# control-surface-left.net
KiCad netlist of a schematic drawn in EAGLE
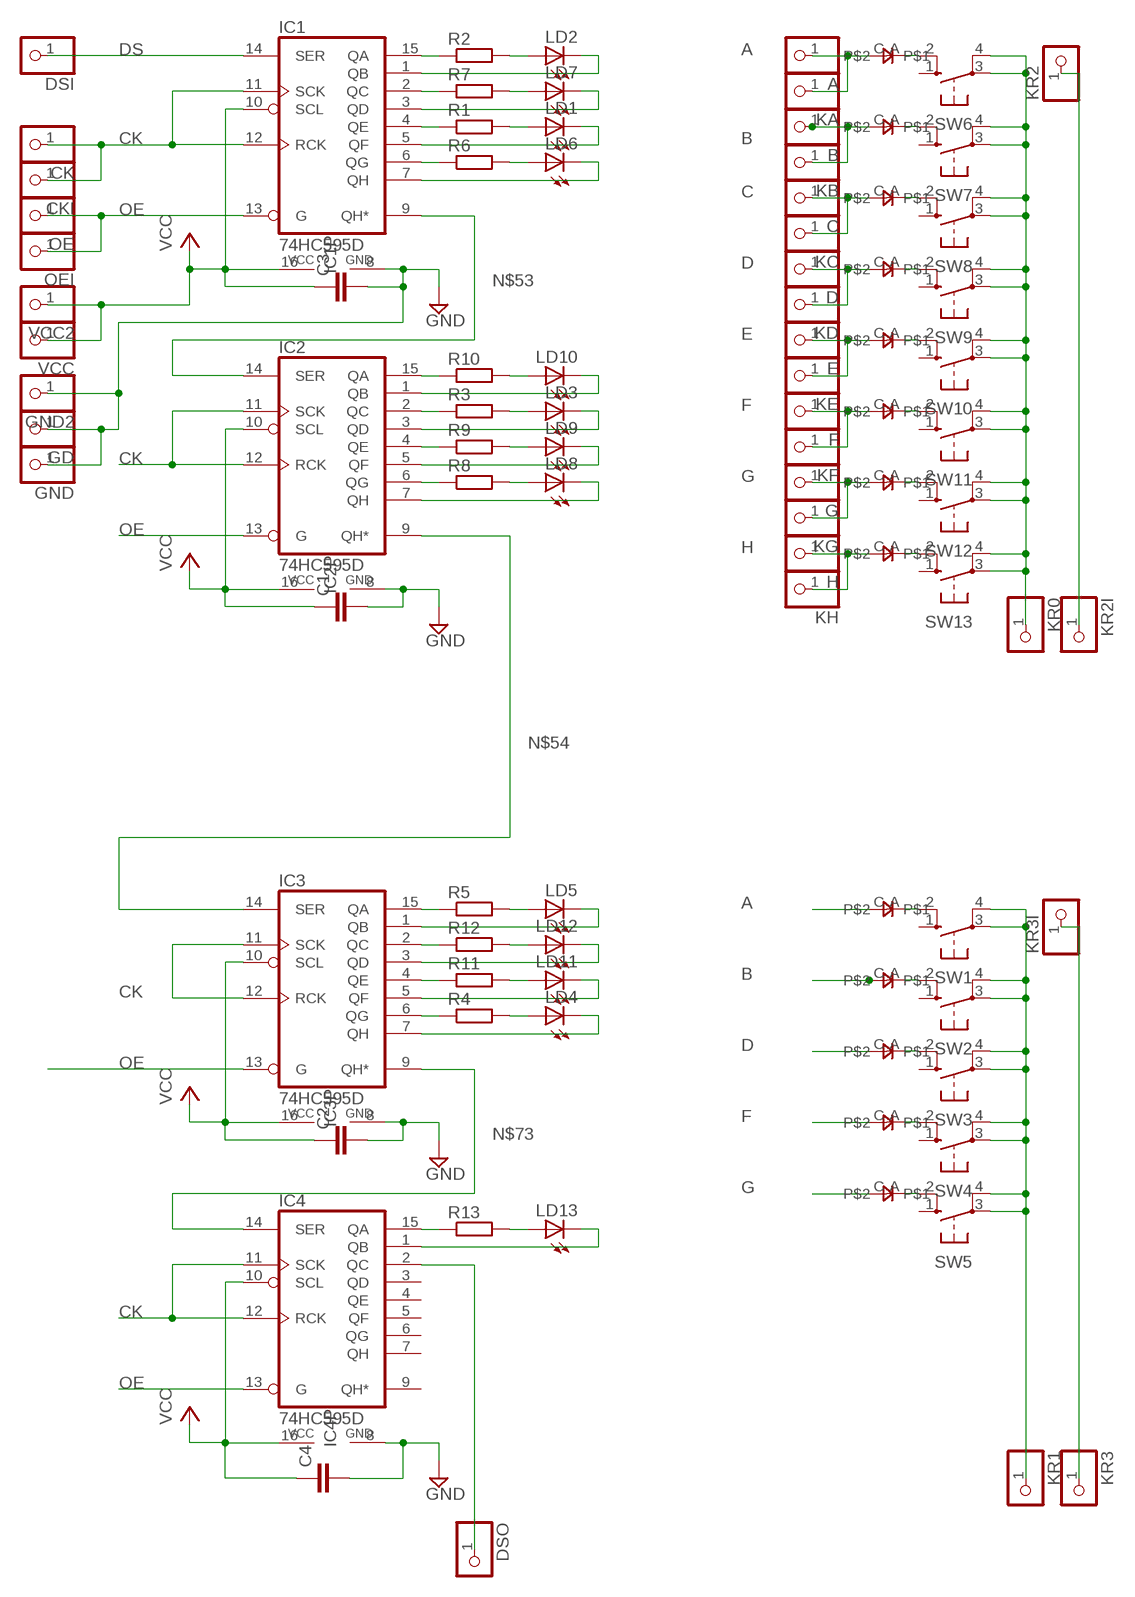
[diagram p0: schematic, sheet 1]

(export (version "E")
  (design (tool "Eeschema 10.0.6"))
  (components
    (comp (ref "A")
      (value "PINHD-1X1")
      (footprint "eagle-import:1X01")
      (libsource (lib "eagle-import") (part "PINHD-1X1"))
    )
    (comp (ref "B")
      (value "PINHD-1X1")
      (footprint "eagle-import:1X01")
      (libsource (lib "eagle-import") (part "PINHD-1X1"))
    )
    (comp (ref "C")
      (value "PINHD-1X1")
      (footprint "eagle-import:1X01")
      (libsource (lib "eagle-import") (part "PINHD-1X1"))
    )
    (comp (ref "C1")
      (value "C-EUC0805")
      (footprint "eagle-import:C0805")
      (libsource (lib "eagle-import") (part "C-EUC0805"))
    )
    (comp (ref "C2")
      (value "C-EUC0805")
      (footprint "eagle-import:C0805")
      (libsource (lib "eagle-import") (part "C-EUC0805"))
    )
    (comp (ref "C3")
      (value "C-EUC0805")
      (footprint "eagle-import:C0805")
      (libsource (lib "eagle-import") (part "C-EUC0805"))
    )
    (comp (ref "C4")
      (value "C-EUC0805")
      (footprint "eagle-import:C0805")
      (libsource (lib "eagle-import") (part "C-EUC0805"))
    )
    (comp (ref "CK")
      (value "PINHD-1X1")
      (footprint "eagle-import:1X01")
      (libsource (lib "eagle-import") (part "PINHD-1X1"))
    )
    (comp (ref "CKI")
      (value "PINHD-1X1")
      (footprint "eagle-import:1X01")
      (libsource (lib "eagle-import") (part "PINHD-1X1"))
    )
    (comp (ref "D")
      (value "PINHD-1X1")
      (footprint "eagle-import:1X01")
      (libsource (lib "eagle-import") (part "PINHD-1X1"))
    )
    (comp (ref "D1")
      (value "0805DIODE")
      (footprint "eagle-import:0805DIODE")
      (libsource (lib "eagle-import") (part "0805DIODE"))
    )
    (comp (ref "D2")
      (value "0805DIODE")
      (footprint "eagle-import:0805DIODE")
      (libsource (lib "eagle-import") (part "0805DIODE"))
    )
    (comp (ref "D3")
      (value "0805DIODE")
      (footprint "eagle-import:0805DIODE")
      (libsource (lib "eagle-import") (part "0805DIODE"))
    )
    (comp (ref "D4")
      (value "0805DIODE")
      (footprint "eagle-import:0805DIODE")
      (libsource (lib "eagle-import") (part "0805DIODE"))
    )
    (comp (ref "D5")
      (value "0805DIODE")
      (footprint "eagle-import:0805DIODE")
      (libsource (lib "eagle-import") (part "0805DIODE"))
    )
    (comp (ref "D6")
      (value "0805DIODE")
      (footprint "eagle-import:0805DIODE")
      (libsource (lib "eagle-import") (part "0805DIODE"))
    )
    (comp (ref "D7")
      (value "0805DIODE")
      (footprint "eagle-import:0805DIODE")
      (libsource (lib "eagle-import") (part "0805DIODE"))
    )
    (comp (ref "D8")
      (value "0805DIODE")
      (footprint "eagle-import:0805DIODE")
      (libsource (lib "eagle-import") (part "0805DIODE"))
    )
    (comp (ref "D9")
      (value "0805DIODE")
      (footprint "eagle-import:0805DIODE")
      (libsource (lib "eagle-import") (part "0805DIODE"))
    )
    (comp (ref "D10")
      (value "0805DIODE")
      (footprint "eagle-import:0805DIODE")
      (libsource (lib "eagle-import") (part "0805DIODE"))
    )
    (comp (ref "D11")
      (value "0805DIODE")
      (footprint "eagle-import:0805DIODE")
      (libsource (lib "eagle-import") (part "0805DIODE"))
    )
    (comp (ref "D12")
      (value "0805DIODE")
      (footprint "eagle-import:0805DIODE")
      (libsource (lib "eagle-import") (part "0805DIODE"))
    )
    (comp (ref "D13")
      (value "0805DIODE")
      (footprint "eagle-import:0805DIODE")
      (libsource (lib "eagle-import") (part "0805DIODE"))
    )
    (comp (ref "DSI")
      (value "PINHD-1X1")
      (footprint "eagle-import:1X01")
      (libsource (lib "eagle-import") (part "PINHD-1X1"))
    )
    (comp (ref "DSO")
      (value "PINHD-1X1")
      (footprint "eagle-import:1X01")
      (libsource (lib "eagle-import") (part "PINHD-1X1"))
    )
    (comp (ref "E")
      (value "PINHD-1X1")
      (footprint "eagle-import:1X01")
      (libsource (lib "eagle-import") (part "PINHD-1X1"))
    )
    (comp (ref "F")
      (value "PINHD-1X1")
      (footprint "eagle-import:1X01")
      (libsource (lib "eagle-import") (part "PINHD-1X1"))
    )
    (comp (ref "G")
      (value "PINHD-1X1")
      (footprint "eagle-import:1X01")
      (libsource (lib "eagle-import") (part "PINHD-1X1"))
    )
    (comp (ref "GD")
      (value "PINHD-1X1")
      (footprint "eagle-import:1X01")
      (libsource (lib "eagle-import") (part "PINHD-1X1"))
    )
    (comp (ref "GND")
      (value "PINHD-1X1")
      (footprint "eagle-import:1X01")
      (libsource (lib "eagle-import") (part "PINHD-1X1"))
    )
    (comp (ref "GND2")
      (value "PINHD-1X1")
      (footprint "eagle-import:1X01")
      (libsource (lib "eagle-import") (part "PINHD-1X1"))
    )
    (comp (ref "H")
      (value "PINHD-1X1")
      (footprint "eagle-import:1X01")
      (libsource (lib "eagle-import") (part "PINHD-1X1"))
    )
    (comp (ref "IC1")
      (value "74HC595D")
      (footprint "eagle-import:SO16")
      (libsource (lib "eagle-import") (part "74595DHC"))
    )
    (comp (ref "IC2")
      (value "74HC595D")
      (footprint "eagle-import:SO16")
      (libsource (lib "eagle-import") (part "74595DHC"))
    )
    (comp (ref "IC3")
      (value "74HC595D")
      (footprint "eagle-import:SO16")
      (libsource (lib "eagle-import") (part "74595DHC"))
    )
    (comp (ref "IC4")
      (value "74HC595D")
      (footprint "eagle-import:SO16")
      (libsource (lib "eagle-import") (part "74595DHC"))
    )
    (comp (ref "KA")
      (value "PINHD-1X1")
      (footprint "eagle-import:1X01")
      (libsource (lib "eagle-import") (part "PINHD-1X1"))
    )
    (comp (ref "KB")
      (value "PINHD-1X1")
      (footprint "eagle-import:1X01")
      (libsource (lib "eagle-import") (part "PINHD-1X1"))
    )
    (comp (ref "KC")
      (value "PINHD-1X1")
      (footprint "eagle-import:1X01")
      (libsource (lib "eagle-import") (part "PINHD-1X1"))
    )
    (comp (ref "KD")
      (value "PINHD-1X1")
      (footprint "eagle-import:1X01")
      (libsource (lib "eagle-import") (part "PINHD-1X1"))
    )
    (comp (ref "KE")
      (value "PINHD-1X1")
      (footprint "eagle-import:1X01")
      (libsource (lib "eagle-import") (part "PINHD-1X1"))
    )
    (comp (ref "KF")
      (value "PINHD-1X1")
      (footprint "eagle-import:1X01")
      (libsource (lib "eagle-import") (part "PINHD-1X1"))
    )
    (comp (ref "KG")
      (value "PINHD-1X1")
      (footprint "eagle-import:1X01")
      (libsource (lib "eagle-import") (part "PINHD-1X1"))
    )
    (comp (ref "KH")
      (value "PINHD-1X1")
      (footprint "eagle-import:1X01")
      (libsource (lib "eagle-import") (part "PINHD-1X1"))
    )
    (comp (ref "KR0")
      (value "PINHD-1X1")
      (footprint "eagle-import:1X01")
      (libsource (lib "eagle-import") (part "PINHD-1X1"))
    )
    (comp (ref "KR1")
      (value "PINHD-1X1")
      (footprint "eagle-import:1X01")
      (libsource (lib "eagle-import") (part "PINHD-1X1"))
    )
    (comp (ref "KR2")
      (value "PINHD-1X1")
      (footprint "eagle-import:1X01")
      (libsource (lib "eagle-import") (part "PINHD-1X1"))
    )
    (comp (ref "KR2I")
      (value "PINHD-1X1")
      (footprint "eagle-import:1X01")
      (libsource (lib "eagle-import") (part "PINHD-1X1"))
    )
    (comp (ref "KR3")
      (value "PINHD-1X1")
      (footprint "eagle-import:1X01")
      (libsource (lib "eagle-import") (part "PINHD-1X1"))
    )
    (comp (ref "KR3I")
      (value "PINHD-1X1")
      (footprint "eagle-import:1X01")
      (libsource (lib "eagle-import") (part "PINHD-1X1"))
    )
    (comp (ref "LD1")
      (value "LED3MM")
      (footprint "eagle-import:LED3MM")
      (libsource (lib "eagle-import") (part "LED3MM"))
    )
    (comp (ref "LD2")
      (value "LED3MM")
      (footprint "eagle-import:LED3MM")
      (libsource (lib "eagle-import") (part "LED3MM"))
    )
    (comp (ref "LD3")
      (value "LED3MM")
      (footprint "eagle-import:LED3MM")
      (libsource (lib "eagle-import") (part "LED3MM"))
    )
    (comp (ref "LD4")
      (value "LED3MM")
      (footprint "eagle-import:LED3MM")
      (libsource (lib "eagle-import") (part "LED3MM"))
    )
    (comp (ref "LD5")
      (value "LED3MM")
      (footprint "eagle-import:LED3MM")
      (libsource (lib "eagle-import") (part "LED3MM"))
    )
    (comp (ref "LD6")
      (value "LED3MM")
      (footprint "eagle-import:LED3MM")
      (libsource (lib "eagle-import") (part "LED3MM"))
    )
    (comp (ref "LD7")
      (value "LED3MM")
      (footprint "eagle-import:LED3MM")
      (libsource (lib "eagle-import") (part "LED3MM"))
    )
    (comp (ref "LD8")
      (value "LED3MM")
      (footprint "eagle-import:LED3MM")
      (libsource (lib "eagle-import") (part "LED3MM"))
    )
    (comp (ref "LD9")
      (value "LED3MM")
      (footprint "eagle-import:LED3MM")
      (libsource (lib "eagle-import") (part "LED3MM"))
    )
    (comp (ref "LD10")
      (value "LED3MM")
      (footprint "eagle-import:LED3MM")
      (libsource (lib "eagle-import") (part "LED3MM"))
    )
    (comp (ref "LD11")
      (value "LED3MM")
      (footprint "eagle-import:LED3MM")
      (libsource (lib "eagle-import") (part "LED3MM"))
    )
    (comp (ref "LD12")
      (value "LED3MM")
      (footprint "eagle-import:LED3MM")
      (libsource (lib "eagle-import") (part "LED3MM"))
    )
    (comp (ref "LD13")
      (value "LED3MM")
      (footprint "eagle-import:LED3MM")
      (libsource (lib "eagle-import") (part "LED3MM"))
    )
    (comp (ref "OE")
      (value "PINHD-1X1")
      (footprint "eagle-import:1X01")
      (libsource (lib "eagle-import") (part "PINHD-1X1"))
    )
    (comp (ref "OEI")
      (value "PINHD-1X1")
      (footprint "eagle-import:1X01")
      (libsource (lib "eagle-import") (part "PINHD-1X1"))
    )
    (comp (ref "R1")
      (value "R-EU_R0805")
      (footprint "eagle-import:R0805")
      (libsource (lib "eagle-import") (part "R-EU_R0805"))
    )
    (comp (ref "R2")
      (value "R-EU_R0805")
      (footprint "eagle-import:R0805")
      (libsource (lib "eagle-import") (part "R-EU_R0805"))
    )
    (comp (ref "R3")
      (value "R-EU_R0805")
      (footprint "eagle-import:R0805")
      (libsource (lib "eagle-import") (part "R-EU_R0805"))
    )
    (comp (ref "R4")
      (value "R-EU_R0805")
      (footprint "eagle-import:R0805")
      (libsource (lib "eagle-import") (part "R-EU_R0805"))
    )
    (comp (ref "R5")
      (value "R-EU_R0805")
      (footprint "eagle-import:R0805")
      (libsource (lib "eagle-import") (part "R-EU_R0805"))
    )
    (comp (ref "R6")
      (value "R-EU_R0805")
      (footprint "eagle-import:R0805")
      (libsource (lib "eagle-import") (part "R-EU_R0805"))
    )
    (comp (ref "R7")
      (value "R-EU_R0805")
      (footprint "eagle-import:R0805")
      (libsource (lib "eagle-import") (part "R-EU_R0805"))
    )
    (comp (ref "R8")
      (value "R-EU_R0805")
      (footprint "eagle-import:R0805")
      (libsource (lib "eagle-import") (part "R-EU_R0805"))
    )
    (comp (ref "R9")
      (value "R-EU_R0805")
      (footprint "eagle-import:R0805")
      (libsource (lib "eagle-import") (part "R-EU_R0805"))
    )
    (comp (ref "R10")
      (value "R-EU_R0805")
      (footprint "eagle-import:R0805")
      (libsource (lib "eagle-import") (part "R-EU_R0805"))
    )
    (comp (ref "R11")
      (value "R-EU_R0805")
      (footprint "eagle-import:R0805")
      (libsource (lib "eagle-import") (part "R-EU_R0805"))
    )
    (comp (ref "R12")
      (value "R-EU_R0805")
      (footprint "eagle-import:R0805")
      (libsource (lib "eagle-import") (part "R-EU_R0805"))
    )
    (comp (ref "R13")
      (value "R-EU_R0805")
      (footprint "eagle-import:R0805")
      (libsource (lib "eagle-import") (part "R-EU_R0805"))
    )
    (comp (ref "SW1")
      (value "40-XX")
      (footprint "eagle-import:B3F-40XX")
      (fields (field (name "MF") "OMRON COMPONENTS USA") (field (name "MPN") "B3F-4000"))
      (libsource (lib "eagle-import") (part "40-XX"))
    )
    (comp (ref "SW2")
      (value "40-XX")
      (footprint "eagle-import:B3F-40XX")
      (fields (field (name "MF") "OMRON COMPONENTS USA") (field (name "MPN") "B3F-4000"))
      (libsource (lib "eagle-import") (part "40-XX"))
    )
    (comp (ref "SW3")
      (value "40-XX")
      (footprint "eagle-import:B3F-40XX")
      (fields (field (name "MF") "OMRON COMPONENTS USA") (field (name "MPN") "B3F-4000"))
      (libsource (lib "eagle-import") (part "40-XX"))
    )
    (comp (ref "SW4")
      (value "40-XX")
      (footprint "eagle-import:B3F-40XX")
      (fields (field (name "MF") "OMRON COMPONENTS USA") (field (name "MPN") "B3F-4000"))
      (libsource (lib "eagle-import") (part "40-XX"))
    )
    (comp (ref "SW5")
      (value "40-XX")
      (footprint "eagle-import:B3F-40XX")
      (fields (field (name "MF") "OMRON COMPONENTS USA") (field (name "MPN") "B3F-4000"))
      (libsource (lib "eagle-import") (part "40-XX"))
    )
    (comp (ref "SW6")
      (value "40-XX")
      (footprint "eagle-import:B3F-40XX")
      (fields (field (name "MF") "OMRON COMPONENTS USA") (field (name "MPN") "B3F-4000"))
      (libsource (lib "eagle-import") (part "40-XX"))
    )
    (comp (ref "SW7")
      (value "40-XX")
      (footprint "eagle-import:B3F-40XX")
      (fields (field (name "MF") "OMRON COMPONENTS USA") (field (name "MPN") "B3F-4000"))
      (libsource (lib "eagle-import") (part "40-XX"))
    )
    (comp (ref "SW8")
      (value "40-XX")
      (footprint "eagle-import:B3F-40XX")
      (fields (field (name "MF") "OMRON COMPONENTS USA") (field (name "MPN") "B3F-4000"))
      (libsource (lib "eagle-import") (part "40-XX"))
    )
    (comp (ref "SW9")
      (value "40-XX")
      (footprint "eagle-import:B3F-40XX")
      (fields (field (name "MF") "OMRON COMPONENTS USA") (field (name "MPN") "B3F-4000"))
      (libsource (lib "eagle-import") (part "40-XX"))
    )
    (comp (ref "SW10")
      (value "40-XX")
      (footprint "eagle-import:B3F-40XX")
      (fields (field (name "MF") "OMRON COMPONENTS USA") (field (name "MPN") "B3F-4000"))
      (libsource (lib "eagle-import") (part "40-XX"))
    )
    (comp (ref "SW11")
      (value "40-XX")
      (footprint "eagle-import:B3F-40XX")
      (fields (field (name "MF") "OMRON COMPONENTS USA") (field (name "MPN") "B3F-4000"))
      (libsource (lib "eagle-import") (part "40-XX"))
    )
    (comp (ref "SW12")
      (value "40-XX")
      (footprint "eagle-import:B3F-40XX")
      (fields (field (name "MF") "OMRON COMPONENTS USA") (field (name "MPN") "B3F-4000"))
      (libsource (lib "eagle-import") (part "40-XX"))
    )
    (comp (ref "SW13")
      (value "40-XX")
      (footprint "eagle-import:B3F-40XX")
      (fields (field (name "MF") "OMRON COMPONENTS USA") (field (name "MPN") "B3F-4000"))
      (libsource (lib "eagle-import") (part "40-XX"))
    )
    (comp (ref "VCC")
      (value "PINHD-1X1")
      (footprint "eagle-import:1X01")
      (libsource (lib "eagle-import") (part "PINHD-1X1"))
    )
    (comp (ref "VCC2")
      (value "PINHD-1X1")
      (footprint "eagle-import:1X01")
      (libsource (lib "eagle-import") (part "PINHD-1X1"))
    )
  )
  (nets
    (net (code "1") (name "/A") (class "Default")
      (node (ref "A") (pin "1") (pinfunction "1_1") (pintype "passive"))
      (node (ref "D1") (pin "C") (pinfunction "P$1_C") (pintype "bidirectional"))
      (node (ref "D6") (pin "C") (pinfunction "P$1_C") (pintype "bidirectional"))
      (node (ref "KA") (pin "1") (pinfunction "1_1") (pintype "passive"))
    )
    (net (code "2") (name "/B") (class "Default")
      (node (ref "B") (pin "1") (pinfunction "1_1") (pintype "passive"))
      (node (ref "D2") (pin "C") (pinfunction "P$1_C") (pintype "bidirectional"))
      (node (ref "D7") (pin "C") (pinfunction "P$1_C") (pintype "bidirectional"))
      (node (ref "KB") (pin "1") (pinfunction "1_1") (pintype "passive"))
    )
    (net (code "3") (name "/C") (class "Default")
      (node (ref "C") (pin "1") (pinfunction "1_1") (pintype "passive"))
      (node (ref "D8") (pin "C") (pinfunction "P$1_C") (pintype "bidirectional"))
      (node (ref "KC") (pin "1") (pinfunction "1_1") (pintype "passive"))
    )
    (net (code "4") (name "/CK") (class "Default")
      (node (ref "CK") (pin "1") (pinfunction "1_1") (pintype "passive"))
      (node (ref "CKI") (pin "1") (pinfunction "1_1") (pintype "passive"))
      (node (ref "IC1") (pin "11") (pinfunction "SCK_11") (pintype "input"))
      (node (ref "IC1") (pin "12") (pinfunction "RCK_12") (pintype "input"))
      (node (ref "IC2") (pin "11") (pinfunction "SCK_11") (pintype "input"))
      (node (ref "IC2") (pin "12") (pinfunction "RCK_12") (pintype "input"))
      (node (ref "IC3") (pin "11") (pinfunction "SCK_11") (pintype "input"))
      (node (ref "IC3") (pin "12") (pinfunction "RCK_12") (pintype "input"))
      (node (ref "IC4") (pin "11") (pinfunction "SCK_11") (pintype "input"))
      (node (ref "IC4") (pin "12") (pinfunction "RCK_12") (pintype "input"))
    )
    (net (code "5") (name "/D") (class "Default")
      (node (ref "D") (pin "1") (pinfunction "1_1") (pintype "passive"))
      (node (ref "D3") (pin "C") (pinfunction "P$1_C") (pintype "bidirectional"))
      (node (ref "D9") (pin "C") (pinfunction "P$1_C") (pintype "bidirectional"))
      (node (ref "KD") (pin "1") (pinfunction "1_1") (pintype "passive"))
    )
    (net (code "6") (name "/DS") (class "Default")
      (node (ref "DSI") (pin "1") (pinfunction "1_1") (pintype "passive"))
      (node (ref "IC1") (pin "14") (pinfunction "SER_14") (pintype "input"))
    )
    (net (code "7") (name "/E") (class "Default")
      (node (ref "D10") (pin "C") (pinfunction "P$1_C") (pintype "bidirectional"))
      (node (ref "E") (pin "1") (pinfunction "1_1") (pintype "passive"))
      (node (ref "KE") (pin "1") (pinfunction "1_1") (pintype "passive"))
    )
    (net (code "8") (name "/F") (class "Default")
      (node (ref "D11") (pin "C") (pinfunction "P$1_C") (pintype "bidirectional"))
      (node (ref "D4") (pin "C") (pinfunction "P$1_C") (pintype "bidirectional"))
      (node (ref "F") (pin "1") (pinfunction "1_1") (pintype "passive"))
      (node (ref "KF") (pin "1") (pinfunction "1_1") (pintype "passive"))
    )
    (net (code "9") (name "/G") (class "Default")
      (node (ref "D12") (pin "C") (pinfunction "P$1_C") (pintype "bidirectional"))
      (node (ref "D5") (pin "C") (pinfunction "P$1_C") (pintype "bidirectional"))
      (node (ref "G") (pin "1") (pinfunction "1_1") (pintype "passive"))
      (node (ref "KG") (pin "1") (pinfunction "1_1") (pintype "passive"))
    )
    (net (code "10") (name "/H") (class "Default")
      (node (ref "D13") (pin "C") (pinfunction "P$1_C") (pintype "bidirectional"))
      (node (ref "H") (pin "1") (pinfunction "1_1") (pintype "passive"))
      (node (ref "KH") (pin "1") (pinfunction "1_1") (pintype "passive"))
    )
    (net (code "11") (name "/N$53") (class "Default")
      (node (ref "IC1") (pin "9") (pinfunction "QH*_9") (pintype "tri_state"))
      (node (ref "IC2") (pin "14") (pinfunction "SER_14") (pintype "input"))
    )
    (net (code "12") (name "/N$54") (class "Default")
      (node (ref "IC2") (pin "9") (pinfunction "QH*_9") (pintype "tri_state"))
      (node (ref "IC3") (pin "14") (pinfunction "SER_14") (pintype "input"))
    )
    (net (code "13") (name "/N$73") (class "Default")
      (node (ref "IC3") (pin "9") (pinfunction "QH*_9") (pintype "tri_state"))
      (node (ref "IC4") (pin "14") (pinfunction "SER_14") (pintype "input"))
    )
    (net (code "14") (name "/OE") (class "Default")
      (node (ref "IC1") (pin "13") (pinfunction "G_13") (pintype "input"))
      (node (ref "IC2") (pin "13") (pinfunction "G_13") (pintype "input"))
      (node (ref "IC3") (pin "13") (pinfunction "G_13") (pintype "input"))
      (node (ref "IC4") (pin "13") (pinfunction "G_13") (pintype "input"))
      (node (ref "OE") (pin "1") (pinfunction "1_1") (pintype "passive"))
      (node (ref "OEI") (pin "1") (pinfunction "1_1") (pintype "passive"))
    )
    (net (code "15") (name "GND") (class "Default")
      (node (ref "C1") (pin "2") (pinfunction "2_2") (pintype "passive"))
      (node (ref "C2") (pin "2") (pinfunction "2_2") (pintype "passive"))
      (node (ref "C3") (pin "2") (pinfunction "2_2") (pintype "passive"))
      (node (ref "C4") (pin "2") (pinfunction "2_2") (pintype "passive"))
      (node (ref "GD") (pin "1") (pinfunction "1_1") (pintype "passive"))
      (node (ref "GND") (pin "1") (pinfunction "1_1") (pintype "passive"))
      (node (ref "GND2") (pin "1") (pinfunction "1_1") (pintype "passive"))
      (node (ref "IC1") (pin "8") (pinfunction "GND_8") (pintype "power_in"))
      (node (ref "IC2") (pin "8") (pinfunction "GND_8") (pintype "power_in"))
      (node (ref "IC3") (pin "8") (pinfunction "GND_8") (pintype "power_in"))
      (node (ref "IC4") (pin "8") (pinfunction "GND_8") (pintype "power_in"))
    )
    (net (code "16") (name "Net-(D1-P$2)") (class "Default")
      (node (ref "D1") (pin "A") (pinfunction "P$2_A") (pintype "bidirectional"))
      (node (ref "SW1") (pin "2") (pinfunction "S1_2") (pintype "passive"))
    )
    (net (code "17") (name "Net-(D2-P$2)") (class "Default")
      (node (ref "D2") (pin "A") (pinfunction "P$2_A") (pintype "bidirectional"))
      (node (ref "SW2") (pin "2") (pinfunction "S1_2") (pintype "passive"))
    )
    (net (code "18") (name "Net-(D3-P$2)") (class "Default")
      (node (ref "D3") (pin "A") (pinfunction "P$2_A") (pintype "bidirectional"))
      (node (ref "SW3") (pin "2") (pinfunction "S1_2") (pintype "passive"))
    )
    (net (code "19") (name "Net-(D4-P$2)") (class "Default")
      (node (ref "D4") (pin "A") (pinfunction "P$2_A") (pintype "bidirectional"))
      (node (ref "SW4") (pin "2") (pinfunction "S1_2") (pintype "passive"))
    )
    (net (code "20") (name "Net-(D5-P$2)") (class "Default")
      (node (ref "D5") (pin "A") (pinfunction "P$2_A") (pintype "bidirectional"))
      (node (ref "SW5") (pin "2") (pinfunction "S1_2") (pintype "passive"))
    )
    (net (code "21") (name "Net-(D6-P$2)") (class "Default")
      (node (ref "D6") (pin "A") (pinfunction "P$2_A") (pintype "bidirectional"))
      (node (ref "SW6") (pin "2") (pinfunction "S1_2") (pintype "passive"))
    )
    (net (code "22") (name "Net-(D7-P$2)") (class "Default")
      (node (ref "D7") (pin "A") (pinfunction "P$2_A") (pintype "bidirectional"))
      (node (ref "SW7") (pin "2") (pinfunction "S1_2") (pintype "passive"))
    )
    (net (code "23") (name "Net-(D8-P$2)") (class "Default")
      (node (ref "D8") (pin "A") (pinfunction "P$2_A") (pintype "bidirectional"))
      (node (ref "SW8") (pin "2") (pinfunction "S1_2") (pintype "passive"))
    )
    (net (code "24") (name "Net-(D9-P$2)") (class "Default")
      (node (ref "D9") (pin "A") (pinfunction "P$2_A") (pintype "bidirectional"))
      (node (ref "SW9") (pin "2") (pinfunction "S1_2") (pintype "passive"))
    )
    (net (code "25") (name "Net-(D10-P$2)") (class "Default")
      (node (ref "D10") (pin "A") (pinfunction "P$2_A") (pintype "bidirectional"))
      (node (ref "SW10") (pin "2") (pinfunction "S1_2") (pintype "passive"))
    )
    (net (code "26") (name "Net-(D11-P$2)") (class "Default")
      (node (ref "D11") (pin "A") (pinfunction "P$2_A") (pintype "bidirectional"))
      (node (ref "SW11") (pin "2") (pinfunction "S1_2") (pintype "passive"))
    )
    (net (code "27") (name "Net-(D12-P$2)") (class "Default")
      (node (ref "D12") (pin "A") (pinfunction "P$2_A") (pintype "bidirectional"))
      (node (ref "SW12") (pin "2") (pinfunction "S1_2") (pintype "passive"))
    )
    (net (code "28") (name "Net-(D13-P$2)") (class "Default")
      (node (ref "D13") (pin "A") (pinfunction "P$2_A") (pintype "bidirectional"))
      (node (ref "SW13") (pin "2") (pinfunction "S1_2") (pintype "passive"))
    )
    (net (code "29") (name "Net-(IC1A-QA)") (class "Default")
      (node (ref "IC1") (pin "15") (pinfunction "QA_15") (pintype "tri_state"))
      (node (ref "R2") (pin "1") (pinfunction "1_1") (pintype "passive"))
    )
    (net (code "30") (name "Net-(IC1A-QB)") (class "Default")
      (node (ref "IC1") (pin "1") (pinfunction "QB_1") (pintype "tri_state"))
      (node (ref "LD2") (pin "K") (pinfunction "C_K") (pintype "passive"))
    )
    (net (code "31") (name "Net-(IC1A-QC)") (class "Default")
      (node (ref "IC1") (pin "2") (pinfunction "QC_2") (pintype "tri_state"))
      (node (ref "R7") (pin "1") (pinfunction "1_1") (pintype "passive"))
    )
    (net (code "32") (name "Net-(IC1A-QD)") (class "Default")
      (node (ref "IC1") (pin "3") (pinfunction "QD_3") (pintype "tri_state"))
      (node (ref "LD7") (pin "K") (pinfunction "C_K") (pintype "passive"))
    )
    (net (code "33") (name "Net-(IC1A-QE)") (class "Default")
      (node (ref "IC1") (pin "4") (pinfunction "QE_4") (pintype "tri_state"))
      (node (ref "R1") (pin "1") (pinfunction "1_1") (pintype "passive"))
    )
    (net (code "34") (name "Net-(IC1A-QF)") (class "Default")
      (node (ref "IC1") (pin "5") (pinfunction "QF_5") (pintype "tri_state"))
      (node (ref "LD1") (pin "K") (pinfunction "C_K") (pintype "passive"))
    )
    (net (code "35") (name "Net-(IC1A-QG)") (class "Default")
      (node (ref "IC1") (pin "6") (pinfunction "QG_6") (pintype "tri_state"))
      (node (ref "R6") (pin "1") (pinfunction "1_1") (pintype "passive"))
    )
    (net (code "36") (name "Net-(IC1A-QH)") (class "Default")
      (node (ref "IC1") (pin "7") (pinfunction "QH_7") (pintype "tri_state"))
      (node (ref "LD6") (pin "K") (pinfunction "C_K") (pintype "passive"))
    )
    (net (code "37") (name "Net-(IC2A-QA)") (class "Default")
      (node (ref "IC2") (pin "15") (pinfunction "QA_15") (pintype "tri_state"))
      (node (ref "R10") (pin "1") (pinfunction "1_1") (pintype "passive"))
    )
    (net (code "38") (name "Net-(IC2A-QB)") (class "Default")
      (node (ref "IC2") (pin "1") (pinfunction "QB_1") (pintype "tri_state"))
      (node (ref "LD10") (pin "K") (pinfunction "C_K") (pintype "passive"))
    )
    (net (code "39") (name "Net-(IC2A-QC)") (class "Default")
      (node (ref "IC2") (pin "2") (pinfunction "QC_2") (pintype "tri_state"))
      (node (ref "R3") (pin "1") (pinfunction "1_1") (pintype "passive"))
    )
    (net (code "40") (name "Net-(IC2A-QD)") (class "Default")
      (node (ref "IC2") (pin "3") (pinfunction "QD_3") (pintype "tri_state"))
      (node (ref "LD3") (pin "K") (pinfunction "C_K") (pintype "passive"))
    )
    (net (code "41") (name "Net-(IC2A-QE)") (class "Default")
      (node (ref "IC2") (pin "4") (pinfunction "QE_4") (pintype "tri_state"))
      (node (ref "R9") (pin "1") (pinfunction "1_1") (pintype "passive"))
    )
    (net (code "42") (name "Net-(IC2A-QF)") (class "Default")
      (node (ref "IC2") (pin "5") (pinfunction "QF_5") (pintype "tri_state"))
      (node (ref "LD9") (pin "K") (pinfunction "C_K") (pintype "passive"))
    )
    (net (code "43") (name "Net-(IC2A-QG)") (class "Default")
      (node (ref "IC2") (pin "6") (pinfunction "QG_6") (pintype "tri_state"))
      (node (ref "R8") (pin "1") (pinfunction "1_1") (pintype "passive"))
    )
    (net (code "44") (name "Net-(IC2A-QH)") (class "Default")
      (node (ref "IC2") (pin "7") (pinfunction "QH_7") (pintype "tri_state"))
      (node (ref "LD8") (pin "K") (pinfunction "C_K") (pintype "passive"))
    )
    (net (code "45") (name "Net-(IC3A-QA)") (class "Default")
      (node (ref "IC3") (pin "15") (pinfunction "QA_15") (pintype "tri_state"))
      (node (ref "R5") (pin "1") (pinfunction "1_1") (pintype "passive"))
    )
    (net (code "46") (name "Net-(IC3A-QB)") (class "Default")
      (node (ref "IC3") (pin "1") (pinfunction "QB_1") (pintype "tri_state"))
      (node (ref "LD5") (pin "K") (pinfunction "C_K") (pintype "passive"))
    )
    (net (code "47") (name "Net-(IC3A-QC)") (class "Default")
      (node (ref "IC3") (pin "2") (pinfunction "QC_2") (pintype "tri_state"))
      (node (ref "R12") (pin "1") (pinfunction "1_1") (pintype "passive"))
    )
    (net (code "48") (name "Net-(IC3A-QD)") (class "Default")
      (node (ref "IC3") (pin "3") (pinfunction "QD_3") (pintype "tri_state"))
      (node (ref "LD12") (pin "K") (pinfunction "C_K") (pintype "passive"))
    )
    (net (code "49") (name "Net-(IC3A-QE)") (class "Default")
      (node (ref "IC3") (pin "4") (pinfunction "QE_4") (pintype "tri_state"))
      (node (ref "R11") (pin "1") (pinfunction "1_1") (pintype "passive"))
    )
    (net (code "50") (name "Net-(IC3A-QF)") (class "Default")
      (node (ref "IC3") (pin "5") (pinfunction "QF_5") (pintype "tri_state"))
      (node (ref "LD11") (pin "K") (pinfunction "C_K") (pintype "passive"))
    )
    (net (code "51") (name "Net-(IC3A-QG)") (class "Default")
      (node (ref "IC3") (pin "6") (pinfunction "QG_6") (pintype "tri_state"))
      (node (ref "R4") (pin "1") (pinfunction "1_1") (pintype "passive"))
    )
    (net (code "52") (name "Net-(IC3A-QH)") (class "Default")
      (node (ref "IC3") (pin "7") (pinfunction "QH_7") (pintype "tri_state"))
      (node (ref "LD4") (pin "K") (pinfunction "C_K") (pintype "passive"))
    )
    (net (code "53") (name "Net-(IC4A-QA)") (class "Default")
      (node (ref "IC4") (pin "15") (pinfunction "QA_15") (pintype "tri_state"))
      (node (ref "R13") (pin "1") (pinfunction "1_1") (pintype "passive"))
    )
    (net (code "54") (name "Net-(IC4A-QB)") (class "Default")
      (node (ref "IC4") (pin "1") (pinfunction "QB_1") (pintype "tri_state"))
      (node (ref "LD13") (pin "K") (pinfunction "C_K") (pintype "passive"))
    )
    (net (code "55") (name "Net-(IC4A-QC)") (class "Default")
      (node (ref "DSO") (pin "1") (pinfunction "1_1") (pintype "passive"))
      (node (ref "IC4") (pin "2") (pinfunction "QC_2") (pintype "tri_state"))
    )
    (net (code "56") (name "Net-(KR2-Pad1)") (class "Default")
      (node (ref "KR2") (pin "1") (pinfunction "1_1") (pintype "passive"))
      (node (ref "KR2I") (pin "1") (pinfunction "1_1") (pintype "passive"))
    )
    (net (code "57") (name "Net-(KR3-Pad1)") (class "Default")
      (node (ref "KR3") (pin "1") (pinfunction "1_1") (pintype "passive"))
      (node (ref "KR3I") (pin "1") (pinfunction "1_1") (pintype "passive"))
    )
    (net (code "58") (name "Net-(LD1-PadA)") (class "Default")
      (node (ref "LD1") (pin "A") (pinfunction "A_A") (pintype "passive"))
      (node (ref "R1") (pin "2") (pinfunction "2_2") (pintype "passive"))
    )
    (net (code "59") (name "Net-(LD2-PadA)") (class "Default")
      (node (ref "LD2") (pin "A") (pinfunction "A_A") (pintype "passive"))
      (node (ref "R2") (pin "2") (pinfunction "2_2") (pintype "passive"))
    )
    (net (code "60") (name "Net-(LD3-PadA)") (class "Default")
      (node (ref "LD3") (pin "A") (pinfunction "A_A") (pintype "passive"))
      (node (ref "R3") (pin "2") (pinfunction "2_2") (pintype "passive"))
    )
    (net (code "61") (name "Net-(LD4-PadA)") (class "Default")
      (node (ref "LD4") (pin "A") (pinfunction "A_A") (pintype "passive"))
      (node (ref "R4") (pin "2") (pinfunction "2_2") (pintype "passive"))
    )
    (net (code "62") (name "Net-(LD5-PadA)") (class "Default")
      (node (ref "LD5") (pin "A") (pinfunction "A_A") (pintype "passive"))
      (node (ref "R5") (pin "2") (pinfunction "2_2") (pintype "passive"))
    )
    (net (code "63") (name "Net-(LD6-PadA)") (class "Default")
      (node (ref "LD6") (pin "A") (pinfunction "A_A") (pintype "passive"))
      (node (ref "R6") (pin "2") (pinfunction "2_2") (pintype "passive"))
    )
    (net (code "64") (name "Net-(LD7-PadA)") (class "Default")
      (node (ref "LD7") (pin "A") (pinfunction "A_A") (pintype "passive"))
      (node (ref "R7") (pin "2") (pinfunction "2_2") (pintype "passive"))
    )
    (net (code "65") (name "Net-(LD8-PadA)") (class "Default")
      (node (ref "LD8") (pin "A") (pinfunction "A_A") (pintype "passive"))
      (node (ref "R8") (pin "2") (pinfunction "2_2") (pintype "passive"))
    )
    (net (code "66") (name "Net-(LD9-PadA)") (class "Default")
      (node (ref "LD9") (pin "A") (pinfunction "A_A") (pintype "passive"))
      (node (ref "R9") (pin "2") (pinfunction "2_2") (pintype "passive"))
    )
    (net (code "67") (name "Net-(LD10-PadA)") (class "Default")
      (node (ref "LD10") (pin "A") (pinfunction "A_A") (pintype "passive"))
      (node (ref "R10") (pin "2") (pinfunction "2_2") (pintype "passive"))
    )
    (net (code "68") (name "Net-(LD11-PadA)") (class "Default")
      (node (ref "LD11") (pin "A") (pinfunction "A_A") (pintype "passive"))
      (node (ref "R11") (pin "2") (pinfunction "2_2") (pintype "passive"))
    )
    (net (code "69") (name "Net-(LD12-PadA)") (class "Default")
      (node (ref "LD12") (pin "A") (pinfunction "A_A") (pintype "passive"))
      (node (ref "R12") (pin "2") (pinfunction "2_2") (pintype "passive"))
    )
    (net (code "70") (name "Net-(LD13-PadA)") (class "Default")
      (node (ref "LD13") (pin "A") (pinfunction "A_A") (pintype "passive"))
      (node (ref "R13") (pin "2") (pinfunction "2_2") (pintype "passive"))
    )
    (net (code "71") (name "Net-(SW1-P)") (class "Default")
      (node (ref "KR1") (pin "1") (pinfunction "1_1") (pintype "passive"))
      (node (ref "SW1") (pin "3") (pinfunction "P_3") (pintype "passive"))
      (node (ref "SW1") (pin "4") (pinfunction "P1_4") (pintype "passive"))
      (node (ref "SW2") (pin "3") (pinfunction "P_3") (pintype "passive"))
      (node (ref "SW2") (pin "4") (pinfunction "P1_4") (pintype "passive"))
      (node (ref "SW3") (pin "3") (pinfunction "P_3") (pintype "passive"))
      (node (ref "SW3") (pin "4") (pinfunction "P1_4") (pintype "passive"))
      (node (ref "SW4") (pin "3") (pinfunction "P_3") (pintype "passive"))
      (node (ref "SW4") (pin "4") (pinfunction "P1_4") (pintype "passive"))
      (node (ref "SW5") (pin "3") (pinfunction "P_3") (pintype "passive"))
      (node (ref "SW5") (pin "4") (pinfunction "P1_4") (pintype "passive"))
    )
    (net (code "72") (name "Net-(SW10-P)") (class "Default")
      (node (ref "KR0") (pin "1") (pinfunction "1_1") (pintype "passive"))
      (node (ref "SW10") (pin "3") (pinfunction "P_3") (pintype "passive"))
      (node (ref "SW10") (pin "4") (pinfunction "P1_4") (pintype "passive"))
      (node (ref "SW11") (pin "3") (pinfunction "P_3") (pintype "passive"))
      (node (ref "SW11") (pin "4") (pinfunction "P1_4") (pintype "passive"))
      (node (ref "SW12") (pin "3") (pinfunction "P_3") (pintype "passive"))
      (node (ref "SW12") (pin "4") (pinfunction "P1_4") (pintype "passive"))
      (node (ref "SW13") (pin "3") (pinfunction "P_3") (pintype "passive"))
      (node (ref "SW13") (pin "4") (pinfunction "P1_4") (pintype "passive"))
      (node (ref "SW6") (pin "3") (pinfunction "P_3") (pintype "passive"))
      (node (ref "SW6") (pin "4") (pinfunction "P1_4") (pintype "passive"))
      (node (ref "SW7") (pin "3") (pinfunction "P_3") (pintype "passive"))
      (node (ref "SW7") (pin "4") (pinfunction "P1_4") (pintype "passive"))
      (node (ref "SW8") (pin "3") (pinfunction "P_3") (pintype "passive"))
      (node (ref "SW8") (pin "4") (pinfunction "P1_4") (pintype "passive"))
      (node (ref "SW9") (pin "3") (pinfunction "P_3") (pintype "passive"))
      (node (ref "SW9") (pin "4") (pinfunction "P1_4") (pintype "passive"))
    )
    (net (code "73") (name "VCC") (class "Default")
      (node (ref "C1") (pin "1") (pinfunction "1_1") (pintype "passive"))
      (node (ref "C2") (pin "1") (pinfunction "1_1") (pintype "passive"))
      (node (ref "C3") (pin "1") (pinfunction "1_1") (pintype "passive"))
      (node (ref "C4") (pin "1") (pinfunction "1_1") (pintype "passive"))
      (node (ref "IC1") (pin "10") (pinfunction "SCL_10") (pintype "input"))
      (node (ref "IC1") (pin "16") (pinfunction "VCC_16") (pintype "power_in"))
      (node (ref "IC2") (pin "10") (pinfunction "SCL_10") (pintype "input"))
      (node (ref "IC2") (pin "16") (pinfunction "VCC_16") (pintype "power_in"))
      (node (ref "IC3") (pin "10") (pinfunction "SCL_10") (pintype "input"))
      (node (ref "IC3") (pin "16") (pinfunction "VCC_16") (pintype "power_in"))
      (node (ref "IC4") (pin "10") (pinfunction "SCL_10") (pintype "input"))
      (node (ref "IC4") (pin "16") (pinfunction "VCC_16") (pintype "power_in"))
      (node (ref "VCC") (pin "1") (pinfunction "1_1") (pintype "passive"))
      (node (ref "VCC2") (pin "1") (pinfunction "1_1") (pintype "passive"))
    )
    (net (code "74") (name "unconnected-(IC4A-QD-Pad3)") (class "Default")
      (node (ref "IC4") (pin "3") (pinfunction "QD_3") (pintype "tri_state"))
    )
    (net (code "75") (name "unconnected-(IC4A-QE-Pad4)") (class "Default")
      (node (ref "IC4") (pin "4") (pinfunction "QE_4") (pintype "tri_state"))
    )
    (net (code "76") (name "unconnected-(IC4A-QF-Pad5)") (class "Default")
      (node (ref "IC4") (pin "5") (pinfunction "QF_5") (pintype "tri_state"))
    )
    (net (code "77") (name "unconnected-(IC4A-QG-Pad6)") (class "Default")
      (node (ref "IC4") (pin "6") (pinfunction "QG_6") (pintype "tri_state"))
    )
    (net (code "78") (name "unconnected-(IC4A-QH*-Pad9)") (class "Default")
      (node (ref "IC4") (pin "9") (pinfunction "QH*_9") (pintype "tri_state"))
    )
    (net (code "79") (name "unconnected-(IC4A-QH-Pad7)") (class "Default")
      (node (ref "IC4") (pin "7") (pinfunction "QH_7") (pintype "tri_state"))
    )
    (net (code "80") (name "unconnected-(SW1-S-Pad1)") (class "Default")
      (node (ref "SW1") (pin "1") (pinfunction "S_1") (pintype "passive"))
    )
    (net (code "81") (name "unconnected-(SW2-S-Pad1)") (class "Default")
      (node (ref "SW2") (pin "1") (pinfunction "S_1") (pintype "passive"))
    )
    (net (code "82") (name "unconnected-(SW3-S-Pad1)") (class "Default")
      (node (ref "SW3") (pin "1") (pinfunction "S_1") (pintype "passive"))
    )
    (net (code "83") (name "unconnected-(SW4-S-Pad1)") (class "Default")
      (node (ref "SW4") (pin "1") (pinfunction "S_1") (pintype "passive"))
    )
    (net (code "84") (name "unconnected-(SW5-S-Pad1)") (class "Default")
      (node (ref "SW5") (pin "1") (pinfunction "S_1") (pintype "passive"))
    )
    (net (code "85") (name "unconnected-(SW6-S-Pad1)") (class "Default")
      (node (ref "SW6") (pin "1") (pinfunction "S_1") (pintype "passive"))
    )
    (net (code "86") (name "unconnected-(SW7-S-Pad1)") (class "Default")
      (node (ref "SW7") (pin "1") (pinfunction "S_1") (pintype "passive"))
    )
    (net (code "87") (name "unconnected-(SW8-S-Pad1)") (class "Default")
      (node (ref "SW8") (pin "1") (pinfunction "S_1") (pintype "passive"))
    )
    (net (code "88") (name "unconnected-(SW9-S-Pad1)") (class "Default")
      (node (ref "SW9") (pin "1") (pinfunction "S_1") (pintype "passive"))
    )
    (net (code "89") (name "unconnected-(SW10-S-Pad1)") (class "Default")
      (node (ref "SW10") (pin "1") (pinfunction "S_1") (pintype "passive"))
    )
    (net (code "90") (name "unconnected-(SW11-S-Pad1)") (class "Default")
      (node (ref "SW11") (pin "1") (pinfunction "S_1") (pintype "passive"))
    )
    (net (code "91") (name "unconnected-(SW12-S-Pad1)") (class "Default")
      (node (ref "SW12") (pin "1") (pinfunction "S_1") (pintype "passive"))
    )
    (net (code "92") (name "unconnected-(SW13-S-Pad1)") (class "Default")
      (node (ref "SW13") (pin "1") (pinfunction "S_1") (pintype "passive"))
    )
  )
)
